# Schematic_tema_tsc.net
KiCad netlist of a schematic drawn in EAGLE
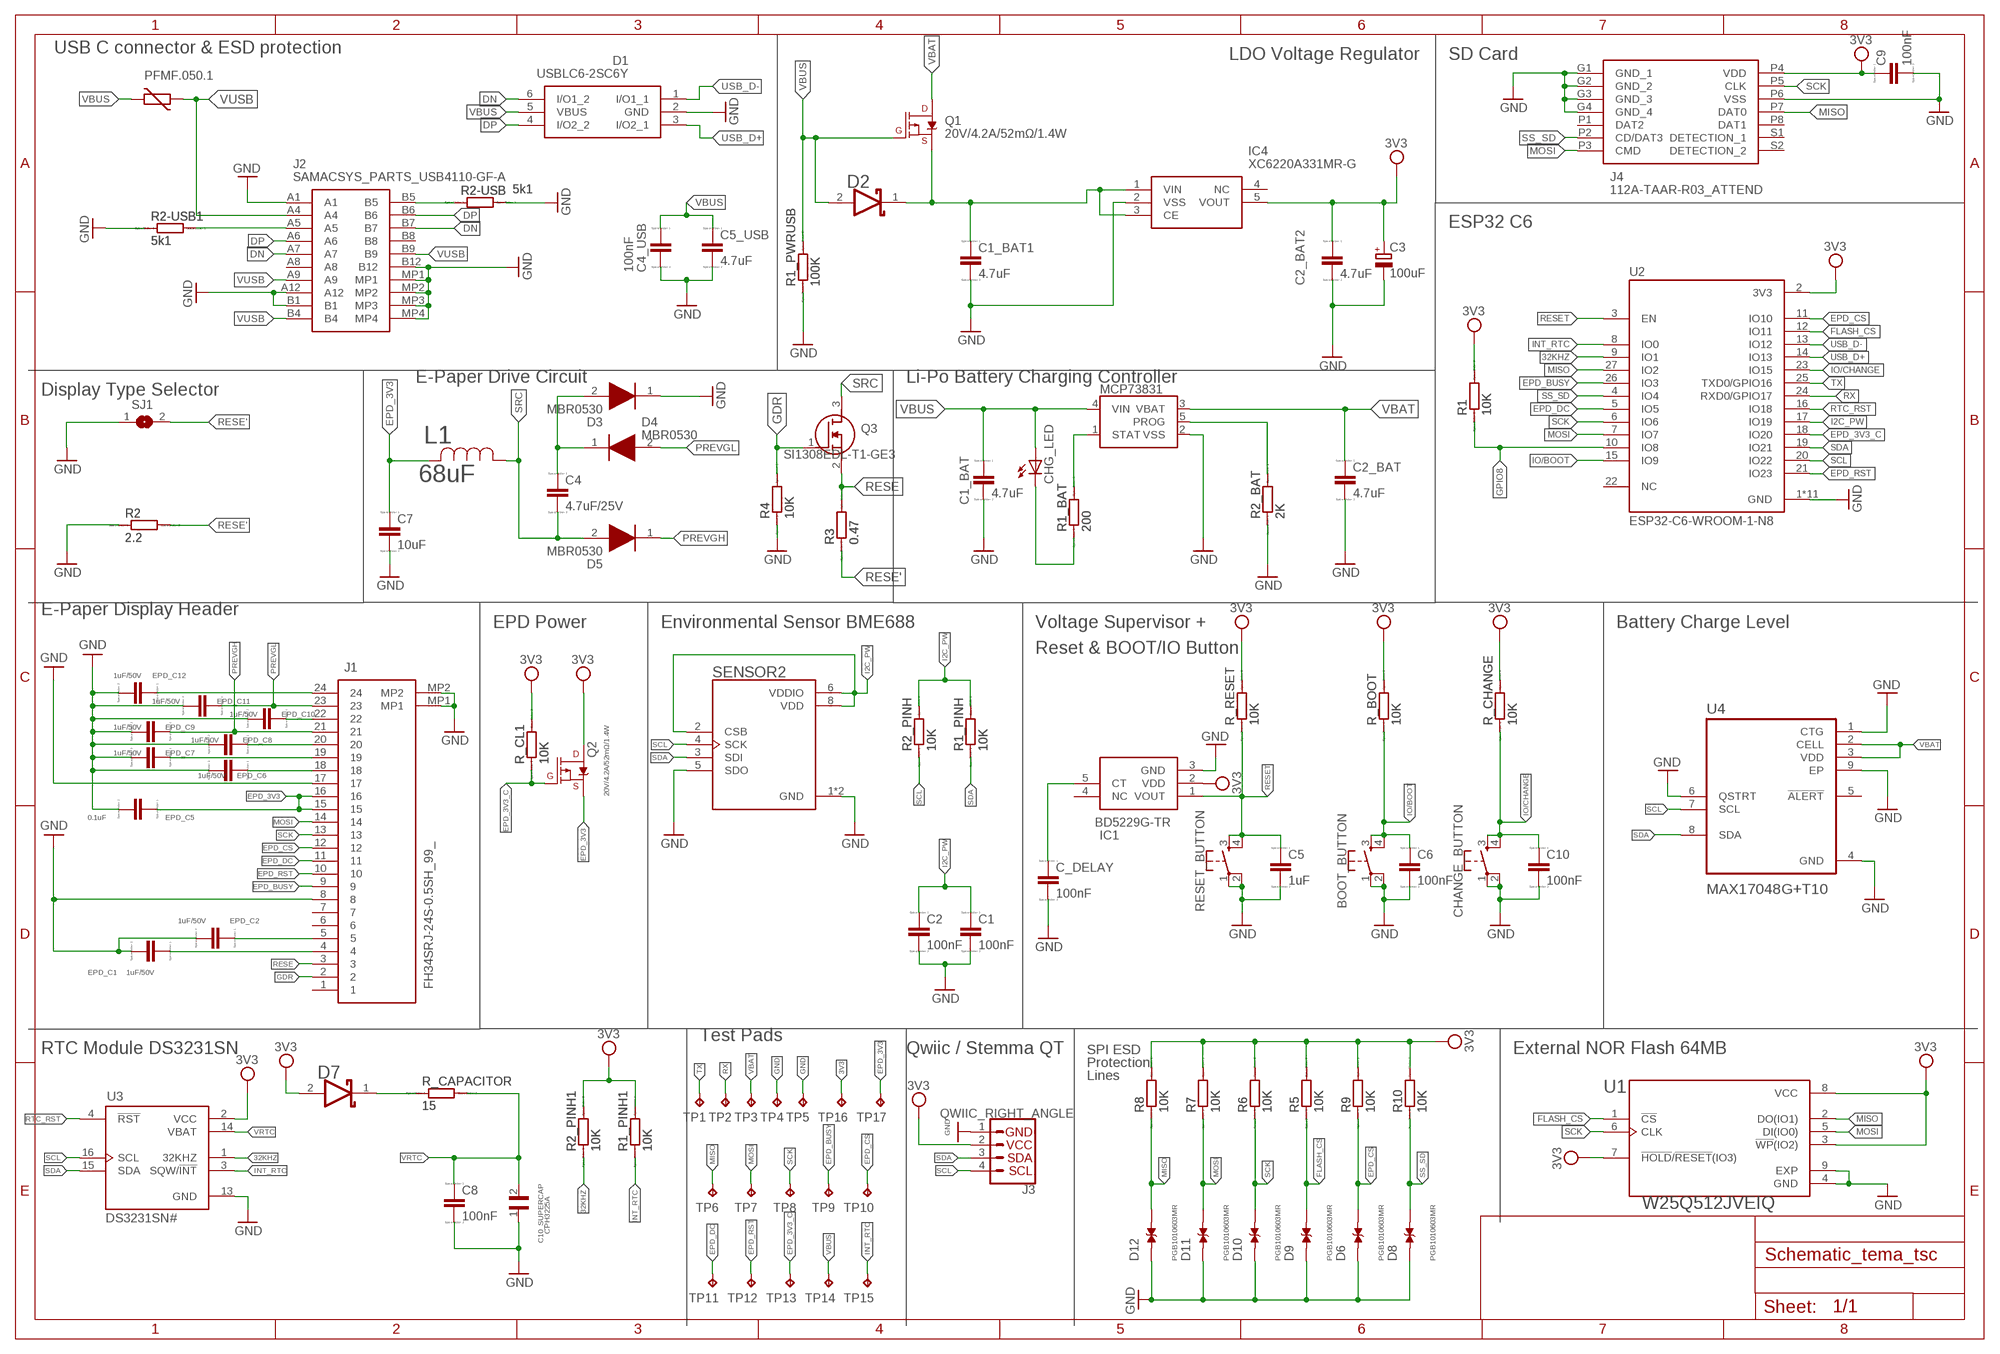
[diagram p0: schematic, sheet 1]

(export (version "E")
  (design (tool "Eeschema 10.0.6"))
  (components
    (comp (ref "BOOT_BUTTON")
      (value "BUTTON_CUSYOMV1")
      (footprint "eagle-import:MYBUTTON")
      (libsource (lib "eagle-import") (part "BUTTON_CUSYOMV1"))
    )
    (comp (ref "C1")
      (value "100nF")
      (footprint "eagle-import:EAGLE-LTSPICE_C0402")
      (libsource (lib "eagle-import") (part "EAGLE-LTSPICE_CC0402"))
    )
    (comp (ref "C1_BAT")
      (value "4.7uF")
      (footprint "eagle-import:EAGLE-LTSPICE_C0402")
      (libsource (lib "eagle-import") (part "EAGLE-LTSPICE_CC0402"))
    )
    (comp (ref "C1_BAT1")
      (value "4.7uF")
      (footprint "eagle-import:EAGLE-LTSPICE_C0402")
      (libsource (lib "eagle-import") (part "EAGLE-LTSPICE_CC0402"))
    )
    (comp (ref "C2")
      (value "100nF")
      (footprint "eagle-import:EAGLE-LTSPICE_C0402")
      (libsource (lib "eagle-import") (part "EAGLE-LTSPICE_CC0402"))
    )
    (comp (ref "C2_BAT")
      (value "4.7uF")
      (footprint "eagle-import:EAGLE-LTSPICE_C0402")
      (libsource (lib "eagle-import") (part "EAGLE-LTSPICE_CC0402"))
    )
    (comp (ref "C2_BAT2")
      (value "4.7uF")
      (footprint "eagle-import:EAGLE-LTSPICE_C0402")
      (libsource (lib "eagle-import") (part "EAGLE-LTSPICE_CC0402"))
    )
    (comp (ref "C3")
      (value "100uF")
      (footprint "eagle-import:RCL_CT3528")
      (libsource (lib "eagle-import") (part "RCL_CPOL-EUCT3528"))
    )
    (comp (ref "C4")
      (value "4.7uF/25V")
      (footprint "eagle-import:EAGLE-LTSPICE_C0402")
      (libsource (lib "eagle-import") (part "EAGLE-LTSPICE_CC0402"))
    )
    (comp (ref "C4_USB")
      (value "100nF")
      (footprint "eagle-import:EAGLE-LTSPICE_C0402")
      (libsource (lib "eagle-import") (part "EAGLE-LTSPICE_CC0402"))
    )
    (comp (ref "C5")
      (value "1uF")
      (footprint "eagle-import:EAGLE-LTSPICE_C0402")
      (libsource (lib "eagle-import") (part "EAGLE-LTSPICE_CC0402"))
    )
    (comp (ref "C5_USB")
      (value "4.7uF")
      (footprint "eagle-import:EAGLE-LTSPICE_C0402")
      (libsource (lib "eagle-import") (part "EAGLE-LTSPICE_CC0402"))
    )
    (comp (ref "C6")
      (value "100nF")
      (footprint "eagle-import:EAGLE-LTSPICE_C0402")
      (libsource (lib "eagle-import") (part "EAGLE-LTSPICE_CC0402"))
    )
    (comp (ref "C7")
      (value "10uF")
      (footprint "eagle-import:EAGLE-LTSPICE_C0402")
      (libsource (lib "eagle-import") (part "EAGLE-LTSPICE_CC0402"))
    )
    (comp (ref "C8")
      (value "100nF")
      (footprint "eagle-import:EAGLE-LTSPICE_C0402")
      (libsource (lib "eagle-import") (part "EAGLE-LTSPICE_CC0402"))
    )
    (comp (ref "C9")
      (value "100nF")
      (footprint "eagle-import:EAGLE-LTSPICE_C0402")
      (libsource (lib "eagle-import") (part "EAGLE-LTSPICE_CC0402"))
    )
    (comp (ref "C10")
      (value "100nF")
      (footprint "eagle-import:EAGLE-LTSPICE_C0402")
      (libsource (lib "eagle-import") (part "EAGLE-LTSPICE_CC0402"))
    )
    (comp (ref "C10_SUPERCAP")
      (value "CPH3225A")
      (footprint "eagle-import:CAPCP3225X100N")
      (fields (field (name "MF") "Seiko Instruments"))
      (libsource (lib "eagle-import") (part "CPH3225A"))
    )
    (comp (ref "CHANGE_BUTTON")
      (value "BUTTON_CUSYOMV1")
      (footprint "eagle-import:MYBUTTON")
      (libsource (lib "eagle-import") (part "BUTTON_CUSYOMV1"))
    )
    (comp (ref "CHG_LED")
      (value "ADAFRUIT_LEDCHIP-LED0603")
      (footprint "eagle-import:ADAFRUIT_CHIP-LED0603")
      (libsource (lib "eagle-import") (part "ADAFRUIT_LEDCHIP-LED0603"))
    )
    (comp (ref "C_DELAY")
      (value "100nF")
      (footprint "eagle-import:EAGLE-LTSPICE_C0402")
      (libsource (lib "eagle-import") (part "EAGLE-LTSPICE_CC0402"))
    )
    (comp (ref "D1")
      (value "USBLC6-2SC6Y")
      (footprint "eagle-import:SOT95P280X145-6N")
      (fields (field (name "MF") "STMicroelectronics"))
      (libsource (lib "eagle-import") (part "USBLC6-2SC6Y"))
    )
    (comp (ref "D2")
      (value "ESP32_WROVER_AVX---SD0805S020S1R0_AVX_SD0805S020S1R0_0_0AVX_SD0805S020S1R0_0_0")
      (footprint "eagle-import:ESP32_WROVER_AVX---SD0805S020S1R0_AVX_SD0805S020S1R0_0")
      (fields
        (field (name "DIGIKEY_PART_NUMBER") "478-7800-1-ND")
        (field (name "MF") "AVX")
        (field (name "MOUSER_PART_NUMBER") "581-SD0805S020S1R0")
      )
      (libsource (lib "eagle-import") (part "ESP32_WROVER_AVX---SD0805S020S1R0_AVX_SD0805S020S1R0_0_0AVX_SD0805S020S1R0_0_0"))
    )
    (comp (ref "D3")
      (value "MBR0530")
      (footprint "eagle-import:SOD3716X135N")
      (fields (field (name "MF") "ON Semiconductor"))
      (libsource (lib "eagle-import") (part "MBR0530"))
    )
    (comp (ref "D4")
      (value "MBR0530")
      (footprint "eagle-import:SOD3716X135N")
      (fields (field (name "MF") "ON Semiconductor"))
      (libsource (lib "eagle-import") (part "MBR0530"))
    )
    (comp (ref "D5")
      (value "MBR0530")
      (footprint "eagle-import:SOD3716X135N")
      (fields (field (name "MF") "ON Semiconductor"))
      (libsource (lib "eagle-import") (part "MBR0530"))
    )
    (comp (ref "D6")
      (value "PGB1010603MR")
      (footprint "eagle-import:DIOC1608X36N")
      (fields (field (name "MF") "Littelfuse Inc."))
      (libsource (lib "eagle-import") (part "PGB1010603MR"))
    )
    (comp (ref "D7")
      (value "ESP32_WROVER_AVX---SD0805S020S1R0_AVX_SD0805S020S1R0_0_0AVX_SD0805S020S1R0_0_0")
      (footprint "eagle-import:ESP32_WROVER_AVX---SD0805S020S1R0_AVX_SD0805S020S1R0_0")
      (fields
        (field (name "DIGIKEY_PART_NUMBER") "478-7800-1-ND")
        (field (name "MF") "AVX")
        (field (name "MOUSER_PART_NUMBER") "581-SD0805S020S1R0")
      )
      (libsource (lib "eagle-import") (part "ESP32_WROVER_AVX---SD0805S020S1R0_AVX_SD0805S020S1R0_0_0AVX_SD0805S020S1R0_0_0"))
    )
    (comp (ref "D8")
      (value "PGB1010603MR")
      (footprint "eagle-import:DIOC1608X36N")
      (fields (field (name "MF") "Littelfuse Inc."))
      (libsource (lib "eagle-import") (part "PGB1010603MR"))
    )
    (comp (ref "D9")
      (value "PGB1010603MR")
      (footprint "eagle-import:DIOC1608X36N")
      (fields (field (name "MF") "Littelfuse Inc."))
      (libsource (lib "eagle-import") (part "PGB1010603MR"))
    )
    (comp (ref "D10")
      (value "PGB1010603MR")
      (footprint "eagle-import:DIOC1608X36N")
      (fields (field (name "MF") "Littelfuse Inc."))
      (libsource (lib "eagle-import") (part "PGB1010603MR"))
    )
    (comp (ref "D11")
      (value "PGB1010603MR")
      (footprint "eagle-import:DIOC1608X36N")
      (fields (field (name "MF") "Littelfuse Inc."))
      (libsource (lib "eagle-import") (part "PGB1010603MR"))
    )
    (comp (ref "D12")
      (value "PGB1010603MR")
      (footprint "eagle-import:DIOC1608X36N")
      (fields (field (name "MF") "Littelfuse Inc."))
      (libsource (lib "eagle-import") (part "PGB1010603MR"))
    )
    (comp (ref "EPD_C1")
      (value "1uF/50V")
      (footprint "eagle-import:EAGLE-LTSPICE_C0402")
      (libsource (lib "eagle-import") (part "EAGLE-LTSPICE_CC0402"))
    )
    (comp (ref "EPD_C2")
      (value "1uF/50V")
      (footprint "eagle-import:EAGLE-LTSPICE_C0402")
      (libsource (lib "eagle-import") (part "EAGLE-LTSPICE_CC0402"))
    )
    (comp (ref "EPD_C5")
      (value "0.1uF")
      (footprint "eagle-import:EAGLE-LTSPICE_C0402")
      (libsource (lib "eagle-import") (part "EAGLE-LTSPICE_CC0402"))
    )
    (comp (ref "EPD_C6")
      (value "1uF/50V")
      (footprint "eagle-import:EAGLE-LTSPICE_C0402")
      (libsource (lib "eagle-import") (part "EAGLE-LTSPICE_CC0402"))
    )
    (comp (ref "EPD_C7")
      (value "1uF/50V")
      (footprint "eagle-import:EAGLE-LTSPICE_C0402")
      (libsource (lib "eagle-import") (part "EAGLE-LTSPICE_CC0402"))
    )
    (comp (ref "EPD_C8")
      (value "1uF/50V")
      (footprint "eagle-import:EAGLE-LTSPICE_C0402")
      (libsource (lib "eagle-import") (part "EAGLE-LTSPICE_CC0402"))
    )
    (comp (ref "EPD_C9")
      (value "1uF/50V")
      (footprint "eagle-import:EAGLE-LTSPICE_C0402")
      (libsource (lib "eagle-import") (part "EAGLE-LTSPICE_CC0402"))
    )
    (comp (ref "EPD_C10")
      (value "1uF/50V")
      (footprint "eagle-import:EAGLE-LTSPICE_C0402")
      (libsource (lib "eagle-import") (part "EAGLE-LTSPICE_CC0402"))
    )
    (comp (ref "EPD_C11")
      (value "1uF/50V")
      (footprint "eagle-import:EAGLE-LTSPICE_C0402")
      (libsource (lib "eagle-import") (part "EAGLE-LTSPICE_CC0402"))
    )
    (comp (ref "EPD_C12")
      (value "1uF/50V")
      (footprint "eagle-import:EAGLE-LTSPICE_C0402")
      (libsource (lib "eagle-import") (part "EAGLE-LTSPICE_CC0402"))
    )
    (comp (ref "IC1")
      (value "BD5229G-TR")
      (footprint "eagle-import:SOT95P280X125-5N")
      (fields (field (name "MOUSER_PART_NUMBER") "755-BD5229G-TR"))
      (libsource (lib "eagle-import") (part "BD5229G-TR"))
    )
    (comp (ref "IC4")
      (value "XC6220A331MR-G")
      (footprint "eagle-import:SOT95P280X120-5N")
      (fields (field (name "MOUSER_PART_NUMBER") "865-XC6220A331MR-G"))
      (libsource (lib "eagle-import") (part "XC6220A331MR-G"))
    )
    (comp (ref "J1")
      (value "FH34SRJ-24S-0.5SH_99_")
      (footprint "eagle-import:FH34SRJ24S05SH99")
      (fields
        (field (name "MANUFACTURER_PART_NUMBER") "FH34SRJ-24S-0.5SH(99)")
        (field (name "MOUSER_PART_NUMBER") "798-FH34SRJ24S05SH99")
      )
      (libsource (lib "eagle-import") (part "FH34SRJ-24S-0.5SH_99_"))
    )
    (comp (ref "J2")
      (value "SAMACSYS_PARTS_USB4110-GF-A")
      (footprint "eagle-import:SAMACSYS_PARTS_USB4110GFA")
      (fields
        (field (name "MANUFACTURER_PART_NUMBER") "USB4110-GF-A")
        (field (name "MOUSER_PART_NUMBER") "640-USB4110-GF-A")
      )
      (libsource (lib "eagle-import") (part "SAMACSYS_PARTS_USB4110-GF-A"))
    )
    (comp (ref "J3")
      (value "QWIIC_RIGHT_ANGLE")
      (footprint "eagle-import:JST04_1MM_RA")
      (libsource (lib "eagle-import") (part "QWIIC_CONNECTORJS-1MM"))
    )
    (comp (ref "J4")
      (value "112A-TAAR-R03_ATTEND")
      (footprint "eagle-import:112ATAARR03ATTEND")
      (fields (field (name "MANUFACTURER_PART_NUMBER") "112A-TAAR-R03 ATTEND"))
      (libsource (lib "eagle-import") (part "112A-TAAR-R03_ATTEND"))
    )
    (comp (ref "L1")
      (value "68uF")
      (footprint "eagle-import:IND_4828-WE-TPC_WRE")
      (fields
        (field (name "MANUFACTURER_PART_NUMBER") "744043680")
        (field (name "COPYRIGHT") "Copyright (C) 2024 Ultra Librarian. All rights reserved.")
      )
      (libsource (lib "eagle-import") (part "744043680IND_4828-WE-TPC_WRE"))
    )
    (comp (ref "MCP73831")
      (value "ESP32_WROVER_SPARKFUN-IC-POWER_MCP73831")
      (footprint "eagle-import:ESP32_WROVER_SPARKFUN-IC-POWER_SOT23-5")
      (libsource (lib "eagle-import") (part "ESP32_WROVER_SPARKFUN-IC-POWER_MCP73831"))
    )
    (comp (ref "PFMF.050.1")
      (value "ESP32C6_VARISTORCN1812")
      (footprint "eagle-import:ESP32C6_VARISTOR_CT_CN1812")
      (libsource (lib "eagle-import") (part "ESP32C6_VARISTORCN1812"))
    )
    (comp (ref "Q1")
      (value "20V/4.2A/52mΩ/1.4W")
      (footprint "eagle-import:ESP32_WROVER_SPARKFUN-DISCRETESEMI_SOT23-3")
      (libsource (lib "eagle-import") (part "ESP32_WROVER_SPARKFUN-DISCRETESEMI_MOSFET_PCH-DMG2305UX-7"))
    )
    (comp (ref "Q2")
      (value "20V/4.2A/52mΩ/1.4W")
      (footprint "eagle-import:ESP32_WROVER_SPARKFUN-DISCRETESEMI_SOT23-3")
      (libsource (lib "eagle-import") (part "ESP32_WROVER_SPARKFUN-DISCRETESEMI_MOSFET_PCH-DMG2305UX-7"))
    )
    (comp (ref "Q3")
      (value "SI1308EDL-T1-GE3")
      (footprint "eagle-import:SOT65P210X110-3N")
      (fields (field (name "MF") "Vishay Siliconix"))
      (libsource (lib "eagle-import") (part "SI1308EDL-T1-GE3"))
    )
    (comp (ref "R1")
      (value "10K")
      (footprint "eagle-import:ESP32_WROVER_EAGLE-LTSPICE_R0402")
      (libsource (lib "eagle-import") (part "ESP32_WROVER_EAGLE-LTSPICE_RR0402"))
    )
    (comp (ref "R1_BAT")
      (value "200")
      (footprint "eagle-import:ESP32_WROVER_EAGLE-LTSPICE_R0402")
      (libsource (lib "eagle-import") (part "ESP32_WROVER_EAGLE-LTSPICE_RR0402"))
    )
    (comp (ref "R1_PINH")
      (value "10K")
      (footprint "eagle-import:ESP32_WROVER_EAGLE-LTSPICE_R0402")
      (libsource (lib "eagle-import") (part "ESP32_WROVER_EAGLE-LTSPICE_RR0402"))
    )
    (comp (ref "R1_PINH1")
      (value "10K")
      (footprint "eagle-import:ESP32_WROVER_EAGLE-LTSPICE_R0402")
      (libsource (lib "eagle-import") (part "ESP32_WROVER_EAGLE-LTSPICE_RR0402"))
    )
    (comp (ref "R1_PWRUSB")
      (value "100K")
      (footprint "eagle-import:ESP32_WROVER_EAGLE-LTSPICE_R0402")
      (libsource (lib "eagle-import") (part "ESP32_WROVER_EAGLE-LTSPICE_RR0402"))
    )
    (comp (ref "R2")
      (value "2.2")
      (footprint "eagle-import:ESP32_WROVER_EAGLE-LTSPICE_R0402")
      (libsource (lib "eagle-import") (part "ESP32_WROVER_EAGLE-LTSPICE_RR0402"))
    )
    (comp (ref "R2-USB")
      (value "5k1")
      (footprint "eagle-import:ESP32_WROVER_EAGLE-LTSPICE_R0402")
      (libsource (lib "eagle-import") (part "ESP32_WROVER_EAGLE-LTSPICE_RR0402"))
    )
    (comp (ref "R2-USB1")
      (value "5k1")
      (footprint "eagle-import:ESP32_WROVER_EAGLE-LTSPICE_R0402")
      (libsource (lib "eagle-import") (part "ESP32_WROVER_EAGLE-LTSPICE_RR0402"))
    )
    (comp (ref "R2_BAT")
      (value "2K")
      (footprint "eagle-import:ESP32_WROVER_EAGLE-LTSPICE_R0402")
      (libsource (lib "eagle-import") (part "ESP32_WROVER_EAGLE-LTSPICE_RR0402"))
    )
    (comp (ref "R2_PINH")
      (value "10K")
      (footprint "eagle-import:ESP32_WROVER_EAGLE-LTSPICE_R0402")
      (libsource (lib "eagle-import") (part "ESP32_WROVER_EAGLE-LTSPICE_RR0402"))
    )
    (comp (ref "R2_PINH1")
      (value "10K")
      (footprint "eagle-import:ESP32_WROVER_EAGLE-LTSPICE_R0402")
      (libsource (lib "eagle-import") (part "ESP32_WROVER_EAGLE-LTSPICE_RR0402"))
    )
    (comp (ref "R3")
      (value "0.47")
      (footprint "eagle-import:ESP32_WROVER_EAGLE-LTSPICE_R0402")
      (libsource (lib "eagle-import") (part "ESP32_WROVER_EAGLE-LTSPICE_RR0402"))
    )
    (comp (ref "R4")
      (value "10K")
      (footprint "eagle-import:ESP32_WROVER_EAGLE-LTSPICE_R0402")
      (libsource (lib "eagle-import") (part "ESP32_WROVER_EAGLE-LTSPICE_RR0402"))
    )
    (comp (ref "R5")
      (value "10K")
      (footprint "eagle-import:ESP32_WROVER_EAGLE-LTSPICE_R0402")
      (libsource (lib "eagle-import") (part "ESP32_WROVER_EAGLE-LTSPICE_RR0402"))
    )
    (comp (ref "R6")
      (value "10K")
      (footprint "eagle-import:ESP32_WROVER_EAGLE-LTSPICE_R0402")
      (libsource (lib "eagle-import") (part "ESP32_WROVER_EAGLE-LTSPICE_RR0402"))
    )
    (comp (ref "R7")
      (value "10K")
      (footprint "eagle-import:ESP32_WROVER_EAGLE-LTSPICE_R0402")
      (libsource (lib "eagle-import") (part "ESP32_WROVER_EAGLE-LTSPICE_RR0402"))
    )
    (comp (ref "R8")
      (value "10K")
      (footprint "eagle-import:ESP32_WROVER_EAGLE-LTSPICE_R0402")
      (libsource (lib "eagle-import") (part "ESP32_WROVER_EAGLE-LTSPICE_RR0402"))
    )
    (comp (ref "R9")
      (value "10K")
      (footprint "eagle-import:ESP32_WROVER_EAGLE-LTSPICE_R0402")
      (libsource (lib "eagle-import") (part "ESP32_WROVER_EAGLE-LTSPICE_RR0402"))
    )
    (comp (ref "R10")
      (value "10K")
      (footprint "eagle-import:ESP32_WROVER_EAGLE-LTSPICE_R0402")
      (libsource (lib "eagle-import") (part "ESP32_WROVER_EAGLE-LTSPICE_RR0402"))
    )
    (comp (ref "RESET_BUTTON")
      (value "BUTTON_CUSYOMV1")
      (footprint "eagle-import:MYBUTTON")
      (libsource (lib "eagle-import") (part "BUTTON_CUSYOMV1"))
    )
    (comp (ref "R_BOOT")
      (value "10K")
      (footprint "eagle-import:ESP32_WROVER_EAGLE-LTSPICE_R0402")
      (libsource (lib "eagle-import") (part "ESP32_WROVER_EAGLE-LTSPICE_RR0402"))
    )
    (comp (ref "R_CAPACITOR")
      (value "15")
      (footprint "eagle-import:ESP32_WROVER_EAGLE-LTSPICE_R0402")
      (libsource (lib "eagle-import") (part "ESP32_WROVER_EAGLE-LTSPICE_RR0402"))
    )
    (comp (ref "R_CHANGE")
      (value "10K")
      (footprint "eagle-import:ESP32_WROVER_EAGLE-LTSPICE_R0402")
      (libsource (lib "eagle-import") (part "ESP32_WROVER_EAGLE-LTSPICE_RR0402"))
    )
    (comp (ref "R_CL1")
      (value "10K")
      (footprint "eagle-import:ESP32_WROVER_EAGLE-LTSPICE_R0402")
      (libsource (lib "eagle-import") (part "ESP32_WROVER_EAGLE-LTSPICE_RR0402"))
    )
    (comp (ref "R_RESET")
      (value "10K")
      (footprint "eagle-import:ESP32_WROVER_EAGLE-LTSPICE_R0402")
      (libsource (lib "eagle-import") (part "ESP32_WROVER_EAGLE-LTSPICE_RR0402"))
    )
    (comp (ref "SENSOR2")
      (value "ESP32_WROVER_BME680_BME680")
      (footprint "eagle-import:ESP32_WROVER_BME680_PSON80P300X300X100-8N")
      (fields (field (name "MF") "Bosch Sensortec") (field (name "MP") "BME680"))
      (libsource (lib "eagle-import") (part "ESP32_WROVER_BME680_BME680"))
    )
    (comp (ref "SJ1") (value "SJ") (footprint "eagle-import:SJ") (libsource (lib "eagle-import") (part "SJ")))
    (comp (ref "TP1")
      (value "TPTP20R")
      (footprint "eagle-import:TP20R")
      (libsource (lib "eagle-import") (part "TPTP20R"))
    )
    (comp (ref "TP2")
      (value "TPTP20R")
      (footprint "eagle-import:TP20R")
      (libsource (lib "eagle-import") (part "TPTP20R"))
    )
    (comp (ref "TP3")
      (value "TPTP20R")
      (footprint "eagle-import:TP20R")
      (libsource (lib "eagle-import") (part "TPTP20R"))
    )
    (comp (ref "TP4")
      (value "TPTP20R")
      (footprint "eagle-import:TP20R")
      (libsource (lib "eagle-import") (part "TPTP20R"))
    )
    (comp (ref "TP5")
      (value "TPTP20R")
      (footprint "eagle-import:TP20R")
      (libsource (lib "eagle-import") (part "TPTP20R"))
    )
    (comp (ref "TP6")
      (value "TPTP20R")
      (footprint "eagle-import:TP20R")
      (libsource (lib "eagle-import") (part "TPTP20R"))
    )
    (comp (ref "TP7")
      (value "TPTP20R")
      (footprint "eagle-import:TP20R")
      (libsource (lib "eagle-import") (part "TPTP20R"))
    )
    (comp (ref "TP8")
      (value "TPTP20R")
      (footprint "eagle-import:TP20R")
      (libsource (lib "eagle-import") (part "TPTP20R"))
    )
    (comp (ref "TP9")
      (value "TPTP20R")
      (footprint "eagle-import:TP20R")
      (libsource (lib "eagle-import") (part "TPTP20R"))
    )
    (comp (ref "TP10")
      (value "TPTP20R")
      (footprint "eagle-import:TP20R")
      (libsource (lib "eagle-import") (part "TPTP20R"))
    )
    (comp (ref "TP11")
      (value "TPTP20R")
      (footprint "eagle-import:TP20R")
      (libsource (lib "eagle-import") (part "TPTP20R"))
    )
    (comp (ref "TP12")
      (value "TPTP20R")
      (footprint "eagle-import:TP20R")
      (libsource (lib "eagle-import") (part "TPTP20R"))
    )
    (comp (ref "TP13")
      (value "TPTP20R")
      (footprint "eagle-import:TP20R")
      (libsource (lib "eagle-import") (part "TPTP20R"))
    )
    (comp (ref "TP14")
      (value "TPTP20R")
      (footprint "eagle-import:TP20R")
      (libsource (lib "eagle-import") (part "TPTP20R"))
    )
    (comp (ref "TP15")
      (value "TPTP20R")
      (footprint "eagle-import:TP20R")
      (libsource (lib "eagle-import") (part "TPTP20R"))
    )
    (comp (ref "TP16")
      (value "TPTP20R")
      (footprint "eagle-import:TP20R")
      (libsource (lib "eagle-import") (part "TPTP20R"))
    )
    (comp (ref "TP17")
      (value "TPTP20R")
      (footprint "eagle-import:TP20R")
      (libsource (lib "eagle-import") (part "TPTP20R"))
    )
    (comp (ref "U1")
      (value "W25Q512JVEIQ")
      (footprint "eagle-import:SON127P600X800X80-9N")
      (fields (field (name "MF") "Winbond Electronics"))
      (libsource (lib "eagle-import") (part "W25Q512JVEIQ"))
    )
    (comp (ref "U2")
      (value "ESP32-C6-WROOM-1-N8")
      (footprint "eagle-import:XCVR_ESP32-C6-WROOM-1-N8")
      (fields (field (name "MF") "Espressif Systems"))
      (libsource (lib "eagle-import") (part "ESP32-C6-WROOM-1-N8"))
    )
    (comp (ref "U3")
      (value "DS3231SN#")
      (footprint "eagle-import:SOIC127P1032X265-16N")
      (fields (field (name "MF") "Analog Devices"))
      (libsource (lib "eagle-import") (part "DS3231SN#"))
    )
    (comp (ref "U4")
      (value "MAX17048G+T10")
      (footprint "eagle-import:SON50P200X200X80-9N")
      (fields (field (name "MF") "Analog Devices"))
      (libsource (lib "eagle-import") (part "MAX17048G+T10"))
    )
  )
  (nets
    (net (code "1") (name "3V3") (class "Default")
      (node (ref "C2_BAT2") (pin "1") (pinfunction "1_1") (pintype "passive"))
      (node (ref "C3") (pin "+") (pinfunction "+_+") (pintype "passive"))
      (node (ref "C9") (pin "1") (pinfunction "1_1") (pintype "passive"))
      (node (ref "D7") (pin "2") (pinfunction "ANODE_2") (pintype "bidirectional"))
      (node (ref "IC1") (pin "2") (pinfunction "VDD_2") (pintype "bidirectional"))
      (node (ref "IC4") (pin "5") (pinfunction "VOUT_5") (pintype "bidirectional"))
      (node (ref "J3") (pin "2") (pinfunction "2_2") (pintype "power_in"))
      (node (ref "J4") (pin "P4") (pinfunction "VDD_P4") (pintype "bidirectional"))
      (node (ref "Q2") (pin "3") (pinfunction "D_3") (pintype "bidirectional"))
      (node (ref "R1") (pin "2") (pinfunction "2_2") (pintype "passive"))
      (node (ref "R10") (pin "2") (pinfunction "2_2") (pintype "passive"))
      (node (ref "R1_PINH1") (pin "2") (pinfunction "2_2") (pintype "passive"))
      (node (ref "R2_PINH1") (pin "2") (pinfunction "2_2") (pintype "passive"))
      (node (ref "R5") (pin "2") (pinfunction "2_2") (pintype "passive"))
      (node (ref "R6") (pin "2") (pinfunction "2_2") (pintype "passive"))
      (node (ref "R7") (pin "2") (pinfunction "2_2") (pintype "passive"))
      (node (ref "R8") (pin "2") (pinfunction "2_2") (pintype "passive"))
      (node (ref "R9") (pin "2") (pinfunction "2_2") (pintype "passive"))
      (node (ref "R_BOOT") (pin "2") (pinfunction "2_2") (pintype "passive"))
      (node (ref "R_CHANGE") (pin "2") (pinfunction "2_2") (pintype "passive"))
      (node (ref "R_CL1") (pin "2") (pinfunction "2_2") (pintype "passive"))
      (node (ref "R_RESET") (pin "2") (pinfunction "2_2") (pintype "passive"))
      (node (ref "TP16") (pin "TP") (pinfunction "TP_TP") (pintype "input"))
      (node (ref "U1") (pin "3") (pinfunction "~{WP}(IO2)_3") (pintype "bidirectional"))
      (node (ref "U1") (pin "7") (pinfunction "~{HOLD}/~{RESET}(IO3)_7") (pintype "bidirectional"))
      (node (ref "U1") (pin "8") (pinfunction "VCC_8") (pintype "power_in"))
      (node (ref "U2") (pin "2") (pinfunction "3V3_2") (pintype "power_in"))
      (node (ref "U3") (pin "2") (pinfunction "VCC_2") (pintype "power_in"))
    )
    (net (code "2") (name "32KHZ") (class "Default")
      (node (ref "R2_PINH1") (pin "1") (pinfunction "1_1") (pintype "passive"))
      (node (ref "U2") (pin "9") (pinfunction "IO1_9") (pintype "bidirectional"))
      (node (ref "U3") (pin "1") (pinfunction "32KHZ_1") (pintype "output"))
    )
    (net (code "3") (name "DN") (class "Default")
      (node (ref "D1") (pin "6") (pinfunction "I/O1_2_6") (pintype "bidirectional"))
      (node (ref "J2") (pin "A7") (pinfunction "A7_A7") (pintype "bidirectional"))
      (node (ref "J2") (pin "B7") (pinfunction "B7_B7") (pintype "bidirectional"))
    )
    (net (code "4") (name "DP") (class "Default")
      (node (ref "D1") (pin "4") (pinfunction "I/O2_2_4") (pintype "bidirectional"))
      (node (ref "J2") (pin "A6") (pinfunction "A6_A6") (pintype "bidirectional"))
      (node (ref "J2") (pin "B6") (pinfunction "B6_B6") (pintype "bidirectional"))
    )
    (net (code "5") (name "EPD_3V3") (class "Default")
      (node (ref "C7") (pin "1") (pinfunction "1_1") (pintype "passive"))
      (node (ref "EPD_C5") (pin "1") (pinfunction "1_1") (pintype "passive"))
      (node (ref "J1") (pin "15") (pinfunction "15_15") (pintype "bidirectional"))
      (node (ref "J1") (pin "16") (pinfunction "16_16") (pintype "bidirectional"))
      (node (ref "L1") (pin "2") (pinfunction "2_2") (pintype "passive"))
      (node (ref "Q2") (pin "2") (pinfunction "S_2") (pintype "bidirectional"))
      (node (ref "TP17") (pin "TP") (pinfunction "TP_TP") (pintype "input"))
    )
    (net (code "6") (name "EPD_3V3_C") (class "Default")
      (node (ref "Q2") (pin "1") (pinfunction "G_1") (pintype "bidirectional"))
      (node (ref "R_CL1") (pin "1") (pinfunction "1_1") (pintype "passive"))
      (node (ref "TP13") (pin "TP") (pinfunction "TP_TP") (pintype "input"))
      (node (ref "U2") (pin "18") (pinfunction "IO20_18") (pintype "bidirectional"))
    )
    (net (code "7") (name "EPD_BUSY") (class "Default")
      (node (ref "J1") (pin "9") (pinfunction "9_9") (pintype "bidirectional"))
      (node (ref "TP9") (pin "TP") (pinfunction "TP_TP") (pintype "input"))
      (node (ref "U2") (pin "26") (pinfunction "IO3_26") (pintype "bidirectional"))
    )
    (net (code "8") (name "EPD_CS") (class "Default")
      (node (ref "D6") (pin "2") (pinfunction "2_2") (pintype "passive"))
      (node (ref "J1") (pin "12") (pinfunction "12_12") (pintype "bidirectional"))
      (node (ref "R9") (pin "1") (pinfunction "1_1") (pintype "passive"))
      (node (ref "TP10") (pin "TP") (pinfunction "TP_TP") (pintype "input"))
      (node (ref "U2") (pin "11") (pinfunction "IO10_11") (pintype "bidirectional"))
    )
    (net (code "9") (name "EPD_DC") (class "Default")
      (node (ref "J1") (pin "11") (pinfunction "11_11") (pintype "bidirectional"))
      (node (ref "TP11") (pin "TP") (pinfunction "TP_TP") (pintype "input"))
      (node (ref "U2") (pin "5") (pinfunction "IO5_5") (pintype "bidirectional"))
    )
    (net (code "10") (name "EPD_RST") (class "Default")
      (node (ref "J1") (pin "10") (pinfunction "10_10") (pintype "bidirectional"))
      (node (ref "TP12") (pin "TP") (pinfunction "TP_TP") (pintype "input"))
      (node (ref "U2") (pin "21") (pinfunction "IO23_21") (pintype "bidirectional"))
    )
    (net (code "11") (name "FLASH_CS") (class "Default")
      (node (ref "D9") (pin "2") (pinfunction "2_2") (pintype "passive"))
      (node (ref "R5") (pin "1") (pinfunction "1_1") (pintype "passive"))
      (node (ref "U1") (pin "1") (pinfunction "~{CS}_1") (pintype "input"))
      (node (ref "U2") (pin "12") (pinfunction "IO11_12") (pintype "bidirectional"))
    )
    (net (code "12") (name "GDR") (class "Default")
      (node (ref "J1") (pin "2") (pinfunction "2_2") (pintype "bidirectional"))
      (node (ref "Q3") (pin "1") (pinfunction "G_1") (pintype "bidirectional"))
      (node (ref "R4") (pin "2") (pinfunction "2_2") (pintype "passive"))
    )
    (net (code "13") (name "GND") (class "Default")
      (node (ref "BOOT_BUTTON") (pin "1") (pinfunction "1_1") (pintype "passive"))
      (node (ref "BOOT_BUTTON") (pin "2") (pinfunction "2_2") (pintype "passive"))
      (node (ref "C1") (pin "2") (pinfunction "2_2") (pintype "passive"))
      (node (ref "C10") (pin "2") (pinfunction "2_2") (pintype "passive"))
      (node (ref "C10_SUPERCAP") (pin "1") (pinfunction "1_1") (pintype "passive"))
      (node (ref "C1_BAT") (pin "2") (pinfunction "2_2") (pintype "passive"))
      (node (ref "C1_BAT1") (pin "2") (pinfunction "2_2") (pintype "passive"))
      (node (ref "C2") (pin "2") (pinfunction "2_2") (pintype "passive"))
      (node (ref "C2_BAT") (pin "2") (pinfunction "2_2") (pintype "passive"))
      (node (ref "C2_BAT2") (pin "2") (pinfunction "2_2") (pintype "passive"))
      (node (ref "C3") (pin "-") (pinfunction "-_-") (pintype "passive"))
      (node (ref "C4_USB") (pin "2") (pinfunction "2_2") (pintype "passive"))
      (node (ref "C5") (pin "2") (pinfunction "2_2") (pintype "passive"))
      (node (ref "C5_USB") (pin "2") (pinfunction "2_2") (pintype "passive"))
      (node (ref "C6") (pin "2") (pinfunction "2_2") (pintype "passive"))
      (node (ref "C7") (pin "2") (pinfunction "2_2") (pintype "passive"))
      (node (ref "C8") (pin "2") (pinfunction "2_2") (pintype "passive"))
      (node (ref "C9") (pin "2") (pinfunction "2_2") (pintype "passive"))
      (node (ref "CHANGE_BUTTON") (pin "1") (pinfunction "1_1") (pintype "passive"))
      (node (ref "CHANGE_BUTTON") (pin "2") (pinfunction "2_2") (pintype "passive"))
      (node (ref "C_DELAY") (pin "2") (pinfunction "2_2") (pintype "passive"))
      (node (ref "D1") (pin "2") (pinfunction "GND_2") (pintype "bidirectional"))
      (node (ref "D10") (pin "1") (pinfunction "1_1") (pintype "passive"))
      (node (ref "D11") (pin "1") (pinfunction "1_1") (pintype "passive"))
      (node (ref "D12") (pin "1") (pinfunction "1_1") (pintype "passive"))
      (node (ref "D3") (pin "1") (pinfunction "K_1") (pintype "bidirectional"))
      (node (ref "D6") (pin "1") (pinfunction "1_1") (pintype "passive"))
      (node (ref "D8") (pin "1") (pinfunction "1_1") (pintype "passive"))
      (node (ref "D9") (pin "1") (pinfunction "1_1") (pintype "passive"))
      (node (ref "EPD_C1") (pin "2") (pinfunction "2_2") (pintype "passive"))
      (node (ref "EPD_C10") (pin "2") (pinfunction "2_2") (pintype "passive"))
      (node (ref "EPD_C11") (pin "2") (pinfunction "2_2") (pintype "passive"))
      (node (ref "EPD_C12") (pin "2") (pinfunction "2_2") (pintype "passive"))
      (node (ref "EPD_C2") (pin "2") (pinfunction "2_2") (pintype "passive"))
      (node (ref "EPD_C5") (pin "2") (pinfunction "2_2") (pintype "passive"))
      (node (ref "EPD_C6") (pin "2") (pinfunction "2_2") (pintype "passive"))
      (node (ref "EPD_C7") (pin "2") (pinfunction "2_2") (pintype "passive"))
      (node (ref "EPD_C8") (pin "2") (pinfunction "2_2") (pintype "passive"))
      (node (ref "EPD_C9") (pin "2") (pinfunction "2_2") (pintype "passive"))
      (node (ref "IC1") (pin "3") (pinfunction "GND_3") (pintype "bidirectional"))
      (node (ref "IC4") (pin "2") (pinfunction "VSS_2") (pintype "bidirectional"))
      (node (ref "J1") (pin "17") (pinfunction "17_17") (pintype "bidirectional"))
      (node (ref "J1") (pin "8") (pinfunction "8_8") (pintype "bidirectional"))
      (node (ref "J1") (pin "MP1") (pinfunction "MP1_MP1") (pintype "bidirectional"))
      (node (ref "J1") (pin "MP2") (pinfunction "MP2_MP2") (pintype "bidirectional"))
      (node (ref "J2") (pin "A1") (pinfunction "A1_A1") (pintype "bidirectional"))
      (node (ref "J2") (pin "A12") (pinfunction "A12_A12") (pintype "bidirectional"))
      (node (ref "J2") (pin "B1") (pinfunction "B1_B1") (pintype "bidirectional"))
      (node (ref "J2") (pin "B12") (pinfunction "B12_B12") (pintype "bidirectional"))
      (node (ref "J2") (pin "MP1") (pinfunction "MP1_MP1") (pintype "bidirectional"))
      (node (ref "J2") (pin "MP2") (pinfunction "MP2_MP2") (pintype "bidirectional"))
      (node (ref "J2") (pin "MP3") (pinfunction "MP3_MP3") (pintype "bidirectional"))
      (node (ref "J2") (pin "MP4") (pinfunction "MP4_MP4") (pintype "bidirectional"))
      (node (ref "J3") (pin "1") (pinfunction "1_1") (pintype "power_in"))
      (node (ref "J4") (pin "G1") (pinfunction "GND_1_G1") (pintype "bidirectional"))
      (node (ref "J4") (pin "G2") (pinfunction "GND_2_G2") (pintype "bidirectional"))
      (node (ref "J4") (pin "G3") (pinfunction "GND_3_G3") (pintype "bidirectional"))
      (node (ref "J4") (pin "G4") (pinfunction "GND_4_G4") (pintype "bidirectional"))
      (node (ref "J4") (pin "P6") (pinfunction "VSS_P6") (pintype "bidirectional"))
      (node (ref "MCP73831") (pin "2") (pinfunction "VSS_2") (pintype "power_in"))
      (node (ref "R1_PWRUSB") (pin "1") (pinfunction "1_1") (pintype "passive"))
      (node (ref "R2") (pin "1") (pinfunction "1_1") (pintype "passive"))
      (node (ref "R2-USB") (pin "2") (pinfunction "2_2") (pintype "passive"))
      (node (ref "R2-USB1") (pin "1") (pinfunction "1_1") (pintype "passive"))
      (node (ref "R2_BAT") (pin "1") (pinfunction "1_1") (pintype "passive"))
      (node (ref "R4") (pin "1") (pinfunction "1_1") (pintype "passive"))
      (node (ref "RESET_BUTTON") (pin "1") (pinfunction "1_1") (pintype "passive"))
      (node (ref "RESET_BUTTON") (pin "2") (pinfunction "2_2") (pintype "passive"))
      (node (ref "SENSOR2") (pin "1") (pinfunction "GND_1") (pintype "power_in"))
      (node (ref "SENSOR2") (pin "5") (pinfunction "SDO_5") (pintype "bidirectional"))
      (node (ref "SENSOR2") (pin "7") (pinfunction "GND_7") (pintype "power_in"))
      (node (ref "SJ1") (pin "1") (pinfunction "1_1") (pintype "passive"))
      (node (ref "TP4") (pin "TP") (pinfunction "TP_TP") (pintype "input"))
      (node (ref "TP5") (pin "TP") (pinfunction "TP_TP") (pintype "input"))
      (node (ref "U1") (pin "4") (pinfunction "GND_4") (pintype "power_in"))
      (node (ref "U1") (pin "9") (pinfunction "EXP_9") (pintype "passive"))
      (node (ref "U2") (pin "1") (pinfunction "GND_1") (pintype "power_in"))
      (node (ref "U2") (pin "28") (pinfunction "GND_28") (pintype "power_in"))
      (node (ref "U2") (pin "29_1") (pinfunction "GND_29_1") (pintype "power_in"))
      (node (ref "U2") (pin "29_2") (pinfunction "GND_29_2") (pintype "power_in"))
      (node (ref "U2") (pin "29_3") (pinfunction "GND_29_3") (pintype "power_in"))
      (node (ref "U2") (pin "29_4") (pinfunction "GND_29_4") (pintype "power_in"))
      (node (ref "U2") (pin "29_5") (pinfunction "GND_29_5") (pintype "power_in"))
      (node (ref "U2") (pin "29_6") (pinfunction "GND_29_6") (pintype "power_in"))
      (node (ref "U2") (pin "29_7") (pinfunction "GND_29_7") (pintype "power_in"))
      (node (ref "U2") (pin "29_8") (pinfunction "GND_29_8") (pintype "power_in"))
      (node (ref "U2") (pin "29_9") (pinfunction "GND_29_9") (pintype "power_in"))
      (node (ref "U3") (pin "13") (pinfunction "GND_13") (pintype "power_in"))
      (node (ref "U4") (pin "1") (pinfunction "CTG_1") (pintype "power_in"))
      (node (ref "U4") (pin "4") (pinfunction "GND_4") (pintype "power_in"))
      (node (ref "U4") (pin "6") (pinfunction "QSTRT_6") (pintype "input"))
      (node (ref "U4") (pin "9") (pinfunction "EP_9") (pintype "power_in"))
    )
    (net (code "14") (name "GPIO8") (class "Default")
      (node (ref "R1") (pin "1") (pinfunction "1_1") (pintype "passive"))
      (node (ref "U2") (pin "10") (pinfunction "IO8_10") (pintype "bidirectional"))
    )
    (net (code "15") (name "I2C_PW") (class "Default")
      (node (ref "C1") (pin "1") (pinfunction "1_1") (pintype "passive"))
      (node (ref "C2") (pin "1") (pinfunction "1_1") (pintype "passive"))
      (node (ref "R1_PINH") (pin "2") (pinfunction "2_2") (pintype "passive"))
      (node (ref "R2_PINH") (pin "2") (pinfunction "2_2") (pintype "passive"))
      (node (ref "SENSOR2") (pin "2") (pinfunction "CSB_2") (pintype "input"))
      (node (ref "SENSOR2") (pin "6") (pinfunction "VDDIO_6") (pintype "power_in"))
      (node (ref "SENSOR2") (pin "8") (pinfunction "VDD_8") (pintype "power_in"))
      (node (ref "U2") (pin "17") (pinfunction "IO19_17") (pintype "bidirectional"))
    )
    (net (code "16") (name "INT_RTC") (class "Default")
      (node (ref "R1_PINH1") (pin "1") (pinfunction "1_1") (pintype "passive"))
      (node (ref "TP15") (pin "TP") (pinfunction "TP_TP") (pintype "input"))
      (node (ref "U2") (pin "8") (pinfunction "IO0_8") (pintype "bidirectional"))
      (node (ref "U3") (pin "3") (pinfunction "SQW/~{INT}_3") (pintype "output"))
    )
    (net (code "17") (name "IO{slash}BOOT") (class "Default")
      (node (ref "BOOT_BUTTON") (pin "3") (pinfunction "3_3") (pintype "passive"))
      (node (ref "BOOT_BUTTON") (pin "4") (pinfunction "4_4") (pintype "passive"))
      (node (ref "C6") (pin "1") (pinfunction "1_1") (pintype "passive"))
      (node (ref "R_BOOT") (pin "1") (pinfunction "1_1") (pintype "passive"))
      (node (ref "U2") (pin "15") (pinfunction "IO9_15") (pintype "bidirectional"))
    )
    (net (code "18") (name "IO{slash}CHANGE") (class "Default")
      (node (ref "C10") (pin "1") (pinfunction "1_1") (pintype "passive"))
      (node (ref "CHANGE_BUTTON") (pin "3") (pinfunction "3_3") (pintype "passive"))
      (node (ref "CHANGE_BUTTON") (pin "4") (pinfunction "4_4") (pintype "passive"))
      (node (ref "R_CHANGE") (pin "1") (pinfunction "1_1") (pintype "passive"))
      (node (ref "U2") (pin "23") (pinfunction "IO15_23") (pintype "bidirectional"))
    )
    (net (code "19") (name "MISO") (class "Default")
      (node (ref "D12") (pin "2") (pinfunction "2_2") (pintype "passive"))
      (node (ref "J4") (pin "P7") (pinfunction "DAT0_P7") (pintype "bidirectional"))
      (node (ref "R8") (pin "1") (pinfunction "1_1") (pintype "passive"))
      (node (ref "TP6") (pin "TP") (pinfunction "TP_TP") (pintype "input"))
      (node (ref "U1") (pin "2") (pinfunction "DO(IO1)_2") (pintype "bidirectional"))
      (node (ref "U2") (pin "27") (pinfunction "IO2_27") (pintype "bidirectional"))
    )
    (net (code "20") (name "MOSI") (class "Default")
      (node (ref "D11") (pin "2") (pinfunction "2_2") (pintype "passive"))
      (node (ref "J1") (pin "14") (pinfunction "14_14") (pintype "bidirectional"))
      (node (ref "J4") (pin "P3") (pinfunction "CMD_P3") (pintype "bidirectional"))
      (node (ref "R7") (pin "1") (pinfunction "1_1") (pintype "passive"))
      (node (ref "TP7") (pin "TP") (pinfunction "TP_TP") (pintype "input"))
      (node (ref "U1") (pin "5") (pinfunction "DI(IO0)_5") (pintype "bidirectional"))
      (node (ref "U2") (pin "7") (pinfunction "IO7_7") (pintype "bidirectional"))
    )
    (net (code "21") (name "Net-(CHG_LED-PadC)") (class "Default")
      (node (ref "CHG_LED") (pin "C") (pinfunction "C_C") (pintype "passive"))
      (node (ref "R1_BAT") (pin "1") (pinfunction "1_1") (pintype "passive"))
    )
    (net (code "22") (name "Net-(D2-CATHODE)") (class "Default")
      (node (ref "C1_BAT1") (pin "1") (pinfunction "1_1") (pintype "passive"))
      (node (ref "D2") (pin "1") (pinfunction "CATHODE_1") (pintype "bidirectional"))
      (node (ref "IC4") (pin "1") (pinfunction "VIN_1") (pintype "bidirectional"))
      (node (ref "IC4") (pin "3") (pinfunction "CE_3") (pintype "bidirectional"))
      (node (ref "Q1") (pin "2") (pinfunction "S_2") (pintype "bidirectional"))
    )
    (net (code "23") (name "Net-(D3-A)") (class "Default")
      (node (ref "C4") (pin "1") (pinfunction "1_1") (pintype "passive"))
      (node (ref "D3") (pin "2") (pinfunction "A_2") (pintype "bidirectional"))
      (node (ref "D4") (pin "1") (pinfunction "K_1") (pintype "bidirectional"))
    )
    (net (code "24") (name "Net-(D7-CATHODE)") (class "Default")
      (node (ref "D7") (pin "1") (pinfunction "CATHODE_1") (pintype "bidirectional"))
      (node (ref "R_CAPACITOR") (pin "1") (pinfunction "1_1") (pintype "passive"))
    )
    (net (code "25") (name "Net-(EPD_C1-Pad1)") (class "Default")
      (node (ref "EPD_C1") (pin "1") (pinfunction "1_1") (pintype "passive"))
      (node (ref "J1") (pin "4") (pinfunction "4_4") (pintype "bidirectional"))
    )
    (net (code "26") (name "Net-(EPD_C2-Pad1)") (class "Default")
      (node (ref "EPD_C2") (pin "1") (pinfunction "1_1") (pintype "passive"))
      (node (ref "J1") (pin "5") (pinfunction "5_5") (pintype "bidirectional"))
    )
    (net (code "27") (name "Net-(EPD_C6-Pad1)") (class "Default")
      (node (ref "EPD_C6") (pin "1") (pinfunction "1_1") (pintype "passive"))
      (node (ref "J1") (pin "18") (pinfunction "18_18") (pintype "bidirectional"))
    )
    (net (code "28") (name "Net-(EPD_C7-Pad1)") (class "Default")
      (node (ref "EPD_C7") (pin "1") (pinfunction "1_1") (pintype "passive"))
      (node (ref "J1") (pin "19") (pinfunction "19_19") (pintype "bidirectional"))
    )
    (net (code "29") (name "Net-(EPD_C8-Pad1)") (class "Default")
      (node (ref "EPD_C8") (pin "1") (pinfunction "1_1") (pintype "passive"))
      (node (ref "J1") (pin "20") (pinfunction "20_20") (pintype "bidirectional"))
    )
    (net (code "30") (name "Net-(EPD_C10-Pad1)") (class "Default")
      (node (ref "EPD_C10") (pin "1") (pinfunction "1_1") (pintype "passive"))
      (node (ref "J1") (pin "22") (pinfunction "22_22") (pintype "bidirectional"))
    )
    (net (code "31") (name "Net-(EPD_C12-Pad1)") (class "Default")
      (node (ref "EPD_C12") (pin "1") (pinfunction "1_1") (pintype "passive"))
      (node (ref "J1") (pin "24") (pinfunction "24_24") (pintype "bidirectional"))
    )
    (net (code "32") (name "Net-(IC1-CT)") (class "Default")
      (node (ref "C_DELAY") (pin "1") (pinfunction "1_1") (pintype "passive"))
      (node (ref "IC1") (pin "5") (pinfunction "CT_5") (pintype "bidirectional"))
    )
    (net (code "33") (name "Net-(J2-PadA5)") (class "Default")
      (node (ref "J2") (pin "A5") (pinfunction "A5_A5") (pintype "bidirectional"))
      (node (ref "R2-USB1") (pin "2") (pinfunction "2_2") (pintype "passive"))
    )
    (net (code "34") (name "Net-(J2-PadB5)") (class "Default")
      (node (ref "J2") (pin "B5") (pinfunction "B5_B5") (pintype "bidirectional"))
      (node (ref "R2-USB") (pin "1") (pinfunction "1_1") (pintype "passive"))
    )
    (net (code "35") (name "Net-(MCP73831-PROG)") (class "Default")
      (node (ref "MCP73831") (pin "5") (pinfunction "PROG_5") (pintype "input"))
      (node (ref "R2_BAT") (pin "2") (pinfunction "2_2") (pintype "passive"))
    )
    (net (code "36") (name "Net-(MCP73831-STAT)") (class "Default")
      (node (ref "MCP73831") (pin "1") (pinfunction "STAT_1") (pintype "output"))
      (node (ref "R1_BAT") (pin "2") (pinfunction "2_2") (pintype "passive"))
    )
    (net (code "37") (name "PREVGH") (class "Default")
      (node (ref "D5") (pin "1") (pinfunction "K_1") (pintype "bidirectional"))
      (node (ref "EPD_C9") (pin "1") (pinfunction "1_1") (pintype "passive"))
      (node (ref "J1") (pin "21") (pinfunction "21_21") (pintype "bidirectional"))
    )
    (net (code "38") (name "PREVGL") (class "Default")
      (node (ref "D4") (pin "2") (pinfunction "A_2") (pintype "bidirectional"))
      (node (ref "EPD_C11") (pin "1") (pinfunction "1_1") (pintype "passive"))
      (node (ref "J1") (pin "23") (pinfunction "23_23") (pintype "bidirectional"))
    )
    (net (code "39") (name "RESE") (class "Default")
      (node (ref "J1") (pin "3") (pinfunction "3_3") (pintype "bidirectional"))
      (node (ref "Q3") (pin "2") (pinfunction "S_2") (pintype "bidirectional"))
      (node (ref "R3") (pin "2") (pinfunction "2_2") (pintype "passive"))
    )
    (net (code "40") (name "RESE'") (class "Default")
      (node (ref "R2") (pin "2") (pinfunction "2_2") (pintype "passive"))
      (node (ref "R3") (pin "1") (pinfunction "1_1") (pintype "passive"))
      (node (ref "SJ1") (pin "2") (pinfunction "2_2") (pintype "passive"))
    )
    (net (code "41") (name "RESET") (class "Default")
      (node (ref "C5") (pin "1") (pinfunction "1_1") (pintype "passive"))
      (node (ref "IC1") (pin "1") (pinfunction "VOUT_1") (pintype "bidirectional"))
      (node (ref "RESET_BUTTON") (pin "3") (pinfunction "3_3") (pintype "passive"))
      (node (ref "RESET_BUTTON") (pin "4") (pinfunction "4_4") (pintype "passive"))
      (node (ref "R_RESET") (pin "1") (pinfunction "1_1") (pintype "passive"))
      (node (ref "U2") (pin "3") (pinfunction "EN_3") (pintype "input"))
    )
    (net (code "42") (name "RTC_RST") (class "Default")
      (node (ref "U2") (pin "16") (pinfunction "IO18_16") (pintype "bidirectional"))
      (node (ref "U3") (pin "4") (pinfunction "~{RST}_4") (pintype "input"))
    )
    (net (code "43") (name "RX") (class "Default")
      (node (ref "TP2") (pin "TP") (pinfunction "TP_TP") (pintype "input"))
      (node (ref "U2") (pin "24") (pinfunction "RXD0/GPIO17_24") (pintype "bidirectional"))
    )
    (net (code "44") (name "SCK") (class "Default")
      (node (ref "D10") (pin "2") (pinfunction "2_2") (pintype "passive"))
      (node (ref "J1") (pin "13") (pinfunction "13_13") (pintype "bidirectional"))
      (node (ref "J4") (pin "P5") (pinfunction "CLK_P5") (pintype "bidirectional"))
      (node (ref "R6") (pin "1") (pinfunction "1_1") (pintype "passive"))
      (node (ref "TP8") (pin "TP") (pinfunction "TP_TP") (pintype "input"))
      (node (ref "U1") (pin "6") (pinfunction "CLK_6") (pintype "input"))
      (node (ref "U2") (pin "6") (pinfunction "IO6_6") (pintype "bidirectional"))
    )
    (net (code "45") (name "SCL") (class "Default")
      (node (ref "J3") (pin "4") (pinfunction "4_4") (pintype "passive"))
      (node (ref "R2_PINH") (pin "1") (pinfunction "1_1") (pintype "passive"))
      (node (ref "SENSOR2") (pin "4") (pinfunction "SCK_4") (pintype "input"))
      (node (ref "U2") (pin "20") (pinfunction "IO22_20") (pintype "bidirectional"))
      (node (ref "U3") (pin "16") (pinfunction "SCL_16") (pintype "input"))
      (node (ref "U4") (pin "7") (pinfunction "SCL_7") (pintype "input"))
    )
    (net (code "46") (name "SDA") (class "Default")
      (node (ref "J3") (pin "3") (pinfunction "3_3") (pintype "passive"))
      (node (ref "R1_PINH") (pin "1") (pinfunction "1_1") (pintype "passive"))
      (node (ref "SENSOR2") (pin "3") (pinfunction "SDI_3") (pintype "bidirectional"))
      (node (ref "U2") (pin "19") (pinfunction "IO21_19") (pintype "bidirectional"))
      (node (ref "U3") (pin "15") (pinfunction "SDA_15") (pintype "bidirectional"))
      (node (ref "U4") (pin "8") (pinfunction "SDA_8") (pintype "bidirectional"))
    )
    (net (code "47") (name "SRC") (class "Default")
      (node (ref "C4") (pin "2") (pinfunction "2_2") (pintype "passive"))
      (node (ref "D5") (pin "2") (pinfunction "A_2") (pintype "bidirectional"))
      (node (ref "L1") (pin "1") (pinfunction "1_1") (pintype "passive"))
      (node (ref "Q3") (pin "3") (pinfunction "D_3") (pintype "bidirectional"))
    )
    (net (code "48") (name "SS_SD") (class "Default")
      (node (ref "D8") (pin "2") (pinfunction "2_2") (pintype "passive"))
      (node (ref "J4") (pin "P2") (pinfunction "CD/DAT3_P2") (pintype "bidirectional"))
      (node (ref "R10") (pin "1") (pinfunction "1_1") (pintype "passive"))
      (node (ref "U2") (pin "4") (pinfunction "IO4_4") (pintype "bidirectional"))
    )
    (net (code "49") (name "TX") (class "Default")
      (node (ref "TP1") (pin "TP") (pinfunction "TP_TP") (pintype "input"))
      (node (ref "U2") (pin "25") (pinfunction "TXD0/GPIO16_25") (pintype "bidirectional"))
    )
    (net (code "50") (name "USB_D+") (class "Default")
      (node (ref "D1") (pin "3") (pinfunction "I/O2_1_3") (pintype "bidirectional"))
      (node (ref "U2") (pin "14") (pinfunction "IO13_14") (pintype "bidirectional"))
    )
    (net (code "51") (name "USB_D-") (class "Default")
      (node (ref "D1") (pin "1") (pinfunction "I/O1_1_1") (pintype "bidirectional"))
      (node (ref "U2") (pin "13") (pinfunction "IO12_13") (pintype "bidirectional"))
    )
    (net (code "52") (name "VBAT") (class "Default")
      (node (ref "C2_BAT") (pin "1") (pinfunction "1_1") (pintype "passive"))
      (node (ref "MCP73831") (pin "3") (pinfunction "VBAT_3") (pintype "power_in"))
      (node (ref "Q1") (pin "3") (pinfunction "D_3") (pintype "bidirectional"))
      (node (ref "TP3") (pin "TP") (pinfunction "TP_TP") (pintype "input"))
      (node (ref "U4") (pin "2") (pinfunction "CELL_2") (pintype "power_in"))
      (node (ref "U4") (pin "3") (pinfunction "VDD_3") (pintype "power_in"))
    )
    (net (code "53") (name "VBUS") (class "Default")
      (node (ref "C1_BAT") (pin "1") (pinfunction "1_1") (pintype "passive"))
      (node (ref "C4_USB") (pin "1") (pinfunction "1_1") (pintype "passive"))
      (node (ref "C5_USB") (pin "1") (pinfunction "1_1") (pintype "passive"))
      (node (ref "CHG_LED") (pin "A") (pinfunction "A_A") (pintype "passive"))
      (node (ref "D1") (pin "5") (pinfunction "VBUS_5") (pintype "bidirectional"))
      (node (ref "D2") (pin "2") (pinfunction "ANODE_2") (pintype "bidirectional"))
      (node (ref "MCP73831") (pin "4") (pinfunction "VIN_4") (pintype "power_in"))
      (node (ref "PFMF.050.1") (pin "2") (pinfunction "2_2") (pintype "passive"))
      (node (ref "Q1") (pin "1") (pinfunction "G_1") (pintype "bidirectional"))
      (node (ref "R1_PWRUSB") (pin "2") (pinfunction "2_2") (pintype "passive"))
      (node (ref "TP14") (pin "TP") (pinfunction "TP_TP") (pintype "input"))
    )
    (net (code "54") (name "VRTC") (class "Default")
      (node (ref "C10_SUPERCAP") (pin "2") (pinfunction "2_2") (pintype "passive"))
      (node (ref "C8") (pin "1") (pinfunction "1_1") (pintype "passive"))
      (node (ref "R_CAPACITOR") (pin "2") (pinfunction "2_2") (pintype "passive"))
      (node (ref "U3") (pin "14") (pinfunction "VBAT_14") (pintype "power_in"))
    )
    (net (code "55") (name "VUSB") (class "Default")
      (node (ref "J2") (pin "A4") (pinfunction "A4_A4") (pintype "bidirectional"))
      (node (ref "J2") (pin "A9") (pinfunction "A9_A9") (pintype "bidirectional"))
      (node (ref "J2") (pin "B4") (pinfunction "B4_B4") (pintype "bidirectional"))
      (node (ref "J2") (pin "B9") (pinfunction "B9_B9") (pintype "bidirectional"))
      (node (ref "PFMF.050.1") (pin "1") (pinfunction "1_1") (pintype "passive"))
    )
    (net (code "56") (name "unconnected-(IC1-NC-Pad4)") (class "Default")
      (node (ref "IC1") (pin "4") (pinfunction "NC_4") (pintype "no_connect"))
    )
    (net (code "57") (name "unconnected-(IC4-NC-Pad4)") (class "Default")
      (node (ref "IC4") (pin "4") (pinfunction "NC_4") (pintype "no_connect"))
    )
    (net (code "58") (name "unconnected-(J1-Pad1)") (class "Default")
      (node (ref "J1") (pin "1") (pinfunction "1_1") (pintype "bidirectional"))
    )
    (net (code "59") (name "unconnected-(J1-Pad6)") (class "Default")
      (node (ref "J1") (pin "6") (pinfunction "6_6") (pintype "bidirectional"))
    )
    (net (code "60") (name "unconnected-(J1-Pad7)") (class "Default")
      (node (ref "J1") (pin "7") (pinfunction "7_7") (pintype "bidirectional"))
    )
    (net (code "61") (name "unconnected-(J2-PadA8)") (class "Default")
      (node (ref "J2") (pin "A8") (pinfunction "A8_A8") (pintype "bidirectional"))
    )
    (net (code "62") (name "unconnected-(J2-PadB8)") (class "Default")
      (node (ref "J2") (pin "B8") (pinfunction "B8_B8") (pintype "bidirectional"))
    )
    (net (code "63") (name "unconnected-(J4-DAT1-PadP8)") (class "Default")
      (node (ref "J4") (pin "P8") (pinfunction "DAT1_P8") (pintype "bidirectional"))
    )
    (net (code "64") (name "unconnected-(J4-DAT2-PadP1)") (class "Default")
      (node (ref "J4") (pin "P1") (pinfunction "DAT2_P1") (pintype "bidirectional"))
    )
    (net (code "65") (name "unconnected-(J4-DETECTION_1-PadS1)") (class "Default")
      (node (ref "J4") (pin "S1") (pinfunction "DETECTION_1_S1") (pintype "bidirectional"))
    )
    (net (code "66") (name "unconnected-(J4-DETECTION_2-PadS2)") (class "Default")
      (node (ref "J4") (pin "S2") (pinfunction "DETECTION_2_S2") (pintype "bidirectional"))
    )
    (net (code "67") (name "unconnected-(U2-NC-Pad22)") (class "Default")
      (node (ref "U2") (pin "22") (pinfunction "NC_22") (pintype "no_connect"))
    )
    (net (code "68") (name "unconnected-(U4-~{ALERT}-Pad5)") (class "Default")
      (node (ref "U4") (pin "5") (pinfunction "~{ALERT}_5") (pintype "output"))
    )
  )
)
